# A2530.net
KiCad netlist of a schematic drawn in EAGLE
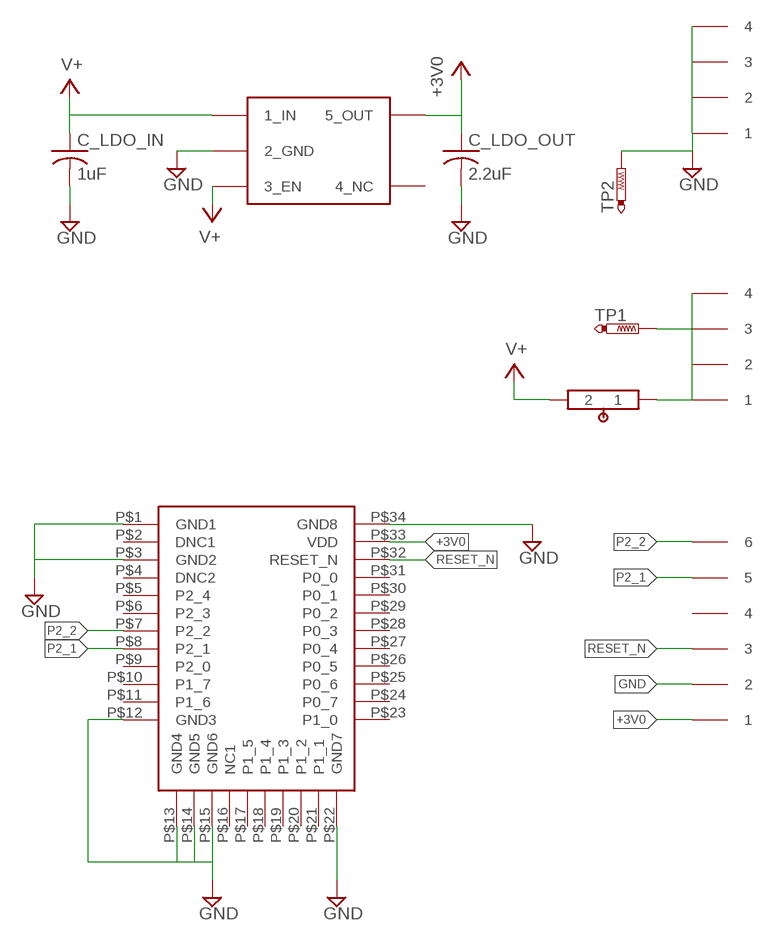
[diagram p0: schematic, sheet 1]

(export (version "E")
  (design (tool "Eeschema 10.0.6"))
  (components
    (comp (ref "C_LDO_IN")
      (value "1uF")
      (footprint "eagle-import:C0603")
      (libsource (lib "eagle-import") (part "C-USC0603"))
    )
    (comp (ref "C_LDO_OUT")
      (value "2.2uF")
      (footprint "eagle-import:C0603")
      (libsource (lib "eagle-import") (part "C-USC0603"))
    )
    (comp (ref "TP1")
      (value "PTR1B2,54")
      (footprint "eagle-import:B2,54")
      (libsource (lib "eagle-import") (part "PTR1B2,54"))
    )
    (comp (ref "TP2")
      (value "PTR1B2,54")
      (footprint "eagle-import:B2,54")
      (libsource (lib "eagle-import") (part "PTR1B2,54"))
    )
    (comp (ref "U$1")
      (value "A2530")
      (footprint "eagle-import:A2530")
      (libsource (lib "eagle-import") (part "A2530"))
    )
    (comp (ref "U$2")
      (value "FFC6POS")
      (footprint "eagle-import:FFC6POS")
      (libsource (lib "eagle-import") (part "FFC6POS"))
    )
    (comp (ref "U$7")
      (value "FFC4POS")
      (footprint "eagle-import:FFC4POS")
      (libsource (lib "eagle-import") (part "FFC4POS"))
    )
    (comp (ref "U$8")
      (value "FFC4POS")
      (footprint "eagle-import:FFC4POS")
      (libsource (lib "eagle-import") (part "FFC4POS"))
    )
    (comp (ref "U$18")
      (value "SWITCH_MANUAL")
      (footprint "eagle-import:SWITCH_MANUAL")
      (libsource (lib "eagle-import") (part "SWITCH_MANUAL"))
    )
    (comp (ref "VREG1")
      (value "REGULATOR")
      (footprint "eagle-import:REGULATOR")
      (libsource (lib "eagle-import") (part "REGULATOR"))
    )
  )
  (nets
    (net (code "1") (name "+3V0") (class "Default")
      (node (ref "C_LDO_OUT") (pin "1") (pinfunction "1_1") (pintype "passive"))
      (node (ref "U$1") (pin "P$33") (pinfunction "VDD_P$33") (pintype "bidirectional"))
      (node (ref "U$2") (pin "1") (pinfunction "1_1") (pintype "bidirectional"))
      (node (ref "VREG1") (pin "5") (pinfunction "5_OUT_5") (pintype "bidirectional"))
    )
    (net (code "2") (name "GND") (class "Default")
      (node (ref "C_LDO_IN") (pin "2") (pinfunction "2_2") (pintype "passive"))
      (node (ref "C_LDO_OUT") (pin "2") (pinfunction "2_2") (pintype "passive"))
      (node (ref "TP2") (pin "TP") (pinfunction "TP_TP") (pintype "input"))
      (node (ref "U$1") (pin "P$1") (pinfunction "GND1_P$1") (pintype "bidirectional"))
      (node (ref "U$1") (pin "P$12") (pinfunction "GND3_P$12") (pintype "bidirectional"))
      (node (ref "U$1") (pin "P$13") (pinfunction "GND4_P$13") (pintype "bidirectional"))
      (node (ref "U$1") (pin "P$14") (pinfunction "GND5_P$14") (pintype "bidirectional"))
      (node (ref "U$1") (pin "P$15") (pinfunction "GND6_P$15") (pintype "bidirectional"))
      (node (ref "U$1") (pin "P$22") (pinfunction "GND7_P$22") (pintype "bidirectional"))
      (node (ref "U$1") (pin "P$3") (pinfunction "GND2_P$3") (pintype "bidirectional"))
      (node (ref "U$1") (pin "P$34") (pinfunction "GND8_P$34") (pintype "bidirectional"))
      (node (ref "U$2") (pin "2") (pinfunction "2_2") (pintype "bidirectional"))
      (node (ref "U$8") (pin "1") (pinfunction "1_1") (pintype "bidirectional"))
      (node (ref "U$8") (pin "2") (pinfunction "2_2") (pintype "bidirectional"))
      (node (ref "U$8") (pin "3") (pinfunction "3_3") (pintype "bidirectional"))
      (node (ref "U$8") (pin "4") (pinfunction "4_4") (pintype "bidirectional"))
      (node (ref "VREG1") (pin "2") (pinfunction "2_GND_2") (pintype "power_in"))
    )
    (net (code "3") (name "Net-(TP1-PadTP)") (class "Default")
      (node (ref "TP1") (pin "TP") (pinfunction "TP_TP") (pintype "input"))
      (node (ref "U$18") (pin "1") (pinfunction "1_1") (pintype "bidirectional"))
      (node (ref "U$7") (pin "1") (pinfunction "1_1") (pintype "bidirectional"))
      (node (ref "U$7") (pin "2") (pinfunction "2_2") (pintype "bidirectional"))
      (node (ref "U$7") (pin "3") (pinfunction "3_3") (pintype "bidirectional"))
      (node (ref "U$7") (pin "4") (pinfunction "4_4") (pintype "bidirectional"))
    )
    (net (code "4") (name "P2_1") (class "Default")
      (node (ref "U$1") (pin "P$8") (pinfunction "P2_1_P$8") (pintype "bidirectional"))
      (node (ref "U$2") (pin "5") (pinfunction "5_5") (pintype "bidirectional"))
    )
    (net (code "5") (name "P2_2") (class "Default")
      (node (ref "U$1") (pin "P$7") (pinfunction "P2_2_P$7") (pintype "bidirectional"))
      (node (ref "U$2") (pin "6") (pinfunction "6_6") (pintype "bidirectional"))
    )
    (net (code "6") (name "RESET_N") (class "Default")
      (node (ref "U$1") (pin "P$32") (pinfunction "RESET_N_P$32") (pintype "bidirectional"))
      (node (ref "U$2") (pin "3") (pinfunction "3_3") (pintype "bidirectional"))
    )
    (net (code "7") (name "V+") (class "Default")
      (node (ref "C_LDO_IN") (pin "1") (pinfunction "1_1") (pintype "passive"))
      (node (ref "U$18") (pin "2") (pinfunction "2_2") (pintype "bidirectional"))
      (node (ref "VREG1") (pin "1") (pinfunction "1_IN_1") (pintype "bidirectional"))
      (node (ref "VREG1") (pin "3") (pinfunction "3_EN_3") (pintype "bidirectional"))
    )
    (net (code "8") (name "unconnected-(U$1-DNC1-PadP$2)") (class "Default")
      (node (ref "U$1") (pin "P$2") (pinfunction "DNC1_P$2") (pintype "bidirectional"))
    )
    (net (code "9") (name "unconnected-(U$1-DNC2-PadP$4)") (class "Default")
      (node (ref "U$1") (pin "P$4") (pinfunction "DNC2_P$4") (pintype "bidirectional"))
    )
    (net (code "10") (name "unconnected-(U$1-NC1-PadP$16)") (class "Default")
      (node (ref "U$1") (pin "P$16") (pinfunction "NC1_P$16") (pintype "bidirectional"))
    )
    (net (code "11") (name "unconnected-(U$1-P0_0-PadP$31)") (class "Default")
      (node (ref "U$1") (pin "P$31") (pinfunction "P0_0_P$31") (pintype "bidirectional"))
    )
    (net (code "12") (name "unconnected-(U$1-P0_1-PadP$30)") (class "Default")
      (node (ref "U$1") (pin "P$30") (pinfunction "P0_1_P$30") (pintype "bidirectional"))
    )
    (net (code "13") (name "unconnected-(U$1-P0_2-PadP$29)") (class "Default")
      (node (ref "U$1") (pin "P$29") (pinfunction "P0_2_P$29") (pintype "bidirectional"))
    )
    (net (code "14") (name "unconnected-(U$1-P0_3-PadP$28)") (class "Default")
      (node (ref "U$1") (pin "P$28") (pinfunction "P0_3_P$28") (pintype "bidirectional"))
    )
    (net (code "15") (name "unconnected-(U$1-P0_4-PadP$27)") (class "Default")
      (node (ref "U$1") (pin "P$27") (pinfunction "P0_4_P$27") (pintype "bidirectional"))
    )
    (net (code "16") (name "unconnected-(U$1-P0_5-PadP$26)") (class "Default")
      (node (ref "U$1") (pin "P$26") (pinfunction "P0_5_P$26") (pintype "bidirectional"))
    )
    (net (code "17") (name "unconnected-(U$1-P0_6-PadP$25)") (class "Default")
      (node (ref "U$1") (pin "P$25") (pinfunction "P0_6_P$25") (pintype "bidirectional"))
    )
    (net (code "18") (name "unconnected-(U$1-P0_7-PadP$24)") (class "Default")
      (node (ref "U$1") (pin "P$24") (pinfunction "P0_7_P$24") (pintype "bidirectional"))
    )
    (net (code "19") (name "unconnected-(U$1-P1_0-PadP$23)") (class "Default")
      (node (ref "U$1") (pin "P$23") (pinfunction "P1_0_P$23") (pintype "bidirectional"))
    )
    (net (code "20") (name "unconnected-(U$1-P1_1-PadP$21)") (class "Default")
      (node (ref "U$1") (pin "P$21") (pinfunction "P1_1_P$21") (pintype "bidirectional"))
    )
    (net (code "21") (name "unconnected-(U$1-P1_2-PadP$20)") (class "Default")
      (node (ref "U$1") (pin "P$20") (pinfunction "P1_2_P$20") (pintype "bidirectional"))
    )
    (net (code "22") (name "unconnected-(U$1-P1_3-PadP$19)") (class "Default")
      (node (ref "U$1") (pin "P$19") (pinfunction "P1_3_P$19") (pintype "bidirectional"))
    )
    (net (code "23") (name "unconnected-(U$1-P1_4-PadP$18)") (class "Default")
      (node (ref "U$1") (pin "P$18") (pinfunction "P1_4_P$18") (pintype "bidirectional"))
    )
    (net (code "24") (name "unconnected-(U$1-P1_5-PadP$17)") (class "Default")
      (node (ref "U$1") (pin "P$17") (pinfunction "P1_5_P$17") (pintype "bidirectional"))
    )
    (net (code "25") (name "unconnected-(U$1-P1_6-PadP$11)") (class "Default")
      (node (ref "U$1") (pin "P$11") (pinfunction "P1_6_P$11") (pintype "bidirectional"))
    )
    (net (code "26") (name "unconnected-(U$1-P1_7-PadP$10)") (class "Default")
      (node (ref "U$1") (pin "P$10") (pinfunction "P1_7_P$10") (pintype "bidirectional"))
    )
    (net (code "27") (name "unconnected-(U$1-P2_0-PadP$9)") (class "Default")
      (node (ref "U$1") (pin "P$9") (pinfunction "P2_0_P$9") (pintype "bidirectional"))
    )
    (net (code "28") (name "unconnected-(U$1-P2_3-PadP$6)") (class "Default")
      (node (ref "U$1") (pin "P$6") (pinfunction "P2_3_P$6") (pintype "bidirectional"))
    )
    (net (code "29") (name "unconnected-(U$1-P2_4-PadP$5)") (class "Default")
      (node (ref "U$1") (pin "P$5") (pinfunction "P2_4_P$5") (pintype "bidirectional"))
    )
    (net (code "30") (name "unconnected-(U$2-Pad4)") (class "Default")
      (node (ref "U$2") (pin "4") (pinfunction "4_4") (pintype "bidirectional"))
    )
    (net (code "31") (name "unconnected-(VREG1-4_NC-Pad4)") (class "Default")
      (node (ref "VREG1") (pin "4") (pinfunction "4_NC_4") (pintype "no_connect"))
    )
  )
)
